# tiva-c.net
KiCad netlist of a schematic drawn in EAGLE
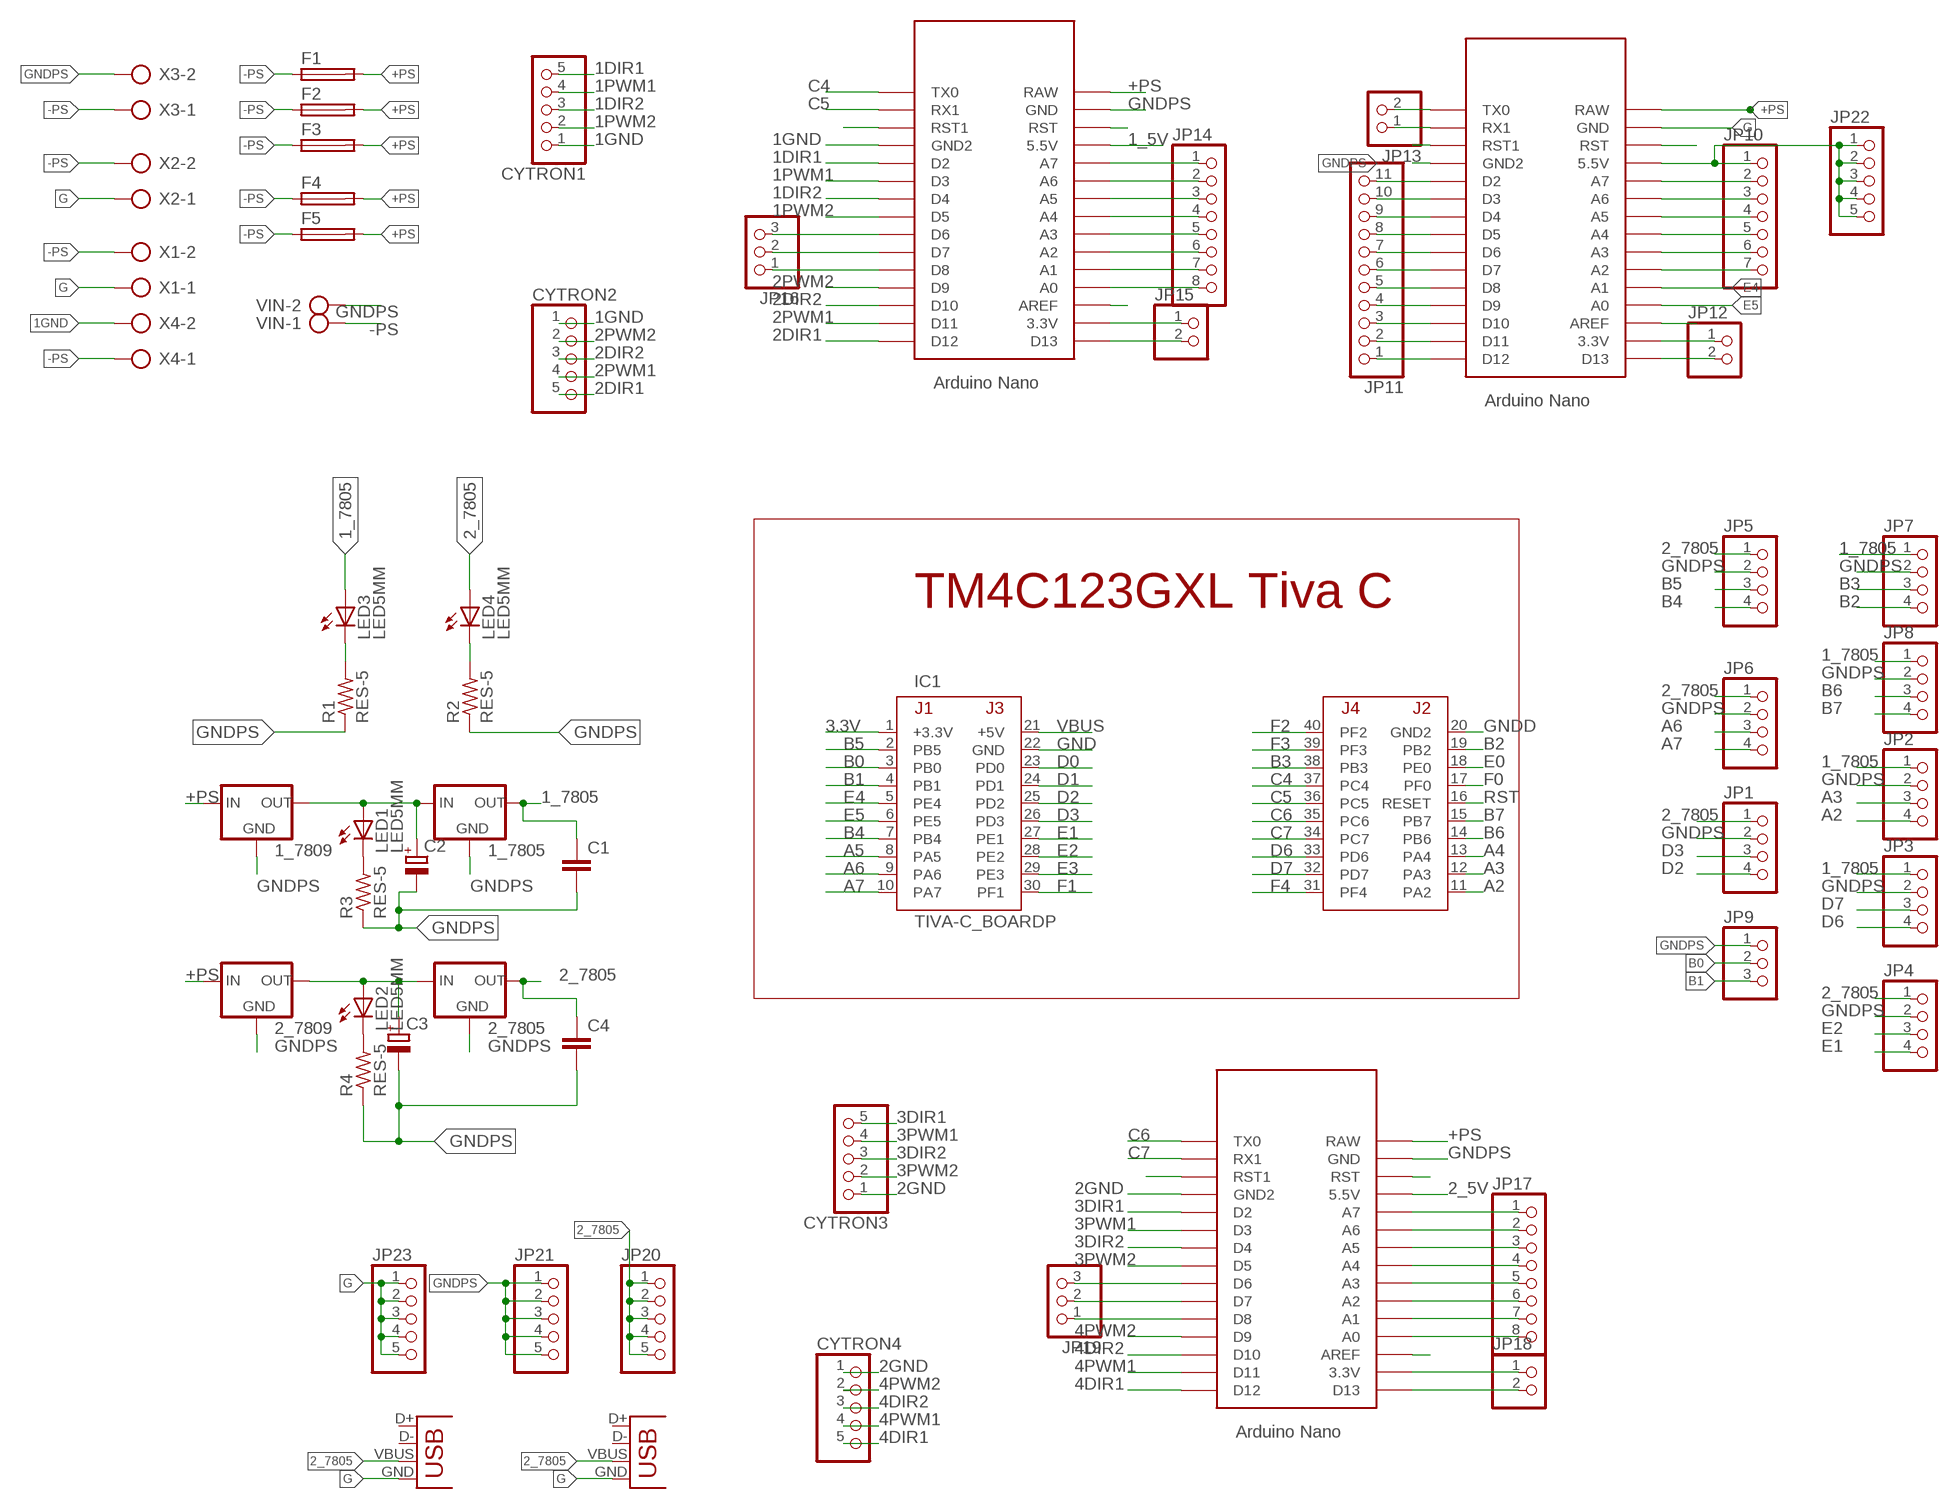
[diagram p0: schematic, sheet 1]

(export (version "E")
  (design (tool "Eeschema 10.0.6"))
  (components
    (comp (ref "1_7805")
      (value "78XXS")
      (footprint "eagle-import:78XXS")
      (libsource (lib "eagle-import") (part "78XXS"))
    )
    (comp (ref "1_7809")
      (value "78XXS")
      (footprint "eagle-import:78XXS")
      (libsource (lib "eagle-import") (part "78XXS"))
    )
    (comp (ref "2_7805")
      (value "78XXS")
      (footprint "eagle-import:78XXS")
      (libsource (lib "eagle-import") (part "78XXS"))
    )
    (comp (ref "2_7809")
      (value "78XXS")
      (footprint "eagle-import:78XXS")
      (libsource (lib "eagle-import") (part "78XXS"))
    )
    (comp (ref "C1")
      (value "CAPACITOR")
      (footprint "eagle-import:C025-025X050")
      (libsource (lib "eagle-import") (part "CAPACITOR"))
    )
    (comp (ref "C2")
      (value "CAP_POL")
      (footprint "eagle-import:E3,5-8")
      (libsource (lib "eagle-import") (part "CAP_POL"))
    )
    (comp (ref "C3")
      (value "CAP_POL")
      (footprint "eagle-import:E3,5-8")
      (libsource (lib "eagle-import") (part "CAP_POL"))
    )
    (comp (ref "C4")
      (value "CAPACITOR")
      (footprint "eagle-import:C025-025X050")
      (libsource (lib "eagle-import") (part "CAPACITOR"))
    )
    (comp (ref "CYTRON1")
      (value "PINHD-1X5")
      (footprint "eagle-import:1X05")
      (libsource (lib "eagle-import") (part "PINHD-1X5"))
    )
    (comp (ref "CYTRON2")
      (value "PINHD-1X5")
      (footprint "eagle-import:1X05")
      (libsource (lib "eagle-import") (part "PINHD-1X5"))
    )
    (comp (ref "CYTRON3")
      (value "PINHD-1X5")
      (footprint "eagle-import:1X05")
      (libsource (lib "eagle-import") (part "PINHD-1X5"))
    )
    (comp (ref "CYTRON4")
      (value "PINHD-1X5")
      (footprint "eagle-import:1X05")
      (libsource (lib "eagle-import") (part "PINHD-1X5"))
    )
    (comp (ref "F1")
      (value "FUSE_HOLDER")
      (footprint "eagle-import:SH22,5A")
      (libsource (lib "eagle-import") (part "FUSE_HOLDER"))
    )
    (comp (ref "F2")
      (value "FUSE_HOLDER")
      (footprint "eagle-import:SH22,5A")
      (libsource (lib "eagle-import") (part "FUSE_HOLDER"))
    )
    (comp (ref "F3")
      (value "FUSE_HOLDER")
      (footprint "eagle-import:SH22,5A")
      (libsource (lib "eagle-import") (part "FUSE_HOLDER"))
    )
    (comp (ref "F4")
      (value "FUSE_HOLDER")
      (footprint "eagle-import:SH22,5A")
      (libsource (lib "eagle-import") (part "FUSE_HOLDER"))
    )
    (comp (ref "F5")
      (value "FUSE_HOLDER")
      (footprint "eagle-import:SH22,5A")
      (libsource (lib "eagle-import") (part "FUSE_HOLDER"))
    )
    (comp (ref "IC1")
      (value "TIVA-C_BOARDP")
      (footprint "eagle-import:TM4C123LAUNCHPAD")
      (fields (field (name "MF") "Texas Instruments") (field (name "MP") "EK-TM4C123GXL"))
      (libsource (lib "eagle-import") (part "TIVA-C_BOARDP"))
    )
    (comp (ref "JP1")
      (value "PINHD-1X4")
      (footprint "eagle-import:1X04")
      (libsource (lib "eagle-import") (part "PINHD-1X4"))
    )
    (comp (ref "JP2")
      (value "PINHD-1X4")
      (footprint "eagle-import:1X04")
      (libsource (lib "eagle-import") (part "PINHD-1X4"))
    )
    (comp (ref "JP3")
      (value "PINHD-1X4")
      (footprint "eagle-import:1X04")
      (libsource (lib "eagle-import") (part "PINHD-1X4"))
    )
    (comp (ref "JP4")
      (value "PINHD-1X4")
      (footprint "eagle-import:1X04")
      (libsource (lib "eagle-import") (part "PINHD-1X4"))
    )
    (comp (ref "JP5")
      (value "PINHD-1X4")
      (footprint "eagle-import:1X04")
      (libsource (lib "eagle-import") (part "PINHD-1X4"))
    )
    (comp (ref "JP6")
      (value "PINHD-1X4")
      (footprint "eagle-import:1X04")
      (libsource (lib "eagle-import") (part "PINHD-1X4"))
    )
    (comp (ref "JP7")
      (value "PINHD-1X4")
      (footprint "eagle-import:1X04")
      (libsource (lib "eagle-import") (part "PINHD-1X4"))
    )
    (comp (ref "JP8")
      (value "PINHD-1X4")
      (footprint "eagle-import:1X04")
      (libsource (lib "eagle-import") (part "PINHD-1X4"))
    )
    (comp (ref "JP9")
      (value "PINHD-1X3")
      (footprint "eagle-import:1X03")
      (libsource (lib "eagle-import") (part "PINHD-1X3"))
    )
    (comp (ref "JP10")
      (value "PINHD-1X7")
      (footprint "eagle-import:1X07")
      (libsource (lib "eagle-import") (part "PINHD-1X7"))
    )
    (comp (ref "JP11")
      (value "PINHD-1X11")
      (footprint "eagle-import:1X11")
      (libsource (lib "eagle-import") (part "PINHD-1X11"))
    )
    (comp (ref "JP12")
      (value "PINHD-1X2")
      (footprint "eagle-import:1X02")
      (libsource (lib "eagle-import") (part "PINHD-1X2"))
    )
    (comp (ref "JP13")
      (value "PINHD-1X2")
      (footprint "eagle-import:1X02")
      (libsource (lib "eagle-import") (part "PINHD-1X2"))
    )
    (comp (ref "JP14")
      (value "PINHD-1X8")
      (footprint "eagle-import:1X08")
      (libsource (lib "eagle-import") (part "PINHD-1X8"))
    )
    (comp (ref "JP15")
      (value "PINHD-1X2")
      (footprint "eagle-import:1X02")
      (libsource (lib "eagle-import") (part "PINHD-1X2"))
    )
    (comp (ref "JP16")
      (value "PINHD-1X3")
      (footprint "eagle-import:1X03")
      (libsource (lib "eagle-import") (part "PINHD-1X3"))
    )
    (comp (ref "JP17")
      (value "PINHD-1X8")
      (footprint "eagle-import:1X08")
      (libsource (lib "eagle-import") (part "PINHD-1X8"))
    )
    (comp (ref "JP18")
      (value "PINHD-1X2")
      (footprint "eagle-import:1X02")
      (libsource (lib "eagle-import") (part "PINHD-1X2"))
    )
    (comp (ref "JP19")
      (value "PINHD-1X3")
      (footprint "eagle-import:1X03")
      (libsource (lib "eagle-import") (part "PINHD-1X3"))
    )
    (comp (ref "JP20")
      (value "PINHD-1X5")
      (footprint "eagle-import:1X05")
      (libsource (lib "eagle-import") (part "PINHD-1X5"))
    )
    (comp (ref "JP21")
      (value "PINHD-1X5")
      (footprint "eagle-import:1X05")
      (libsource (lib "eagle-import") (part "PINHD-1X5"))
    )
    (comp (ref "JP22")
      (value "PINHD-1X5")
      (footprint "eagle-import:1X05")
      (libsource (lib "eagle-import") (part "PINHD-1X5"))
    )
    (comp (ref "JP23")
      (value "PINHD-1X5")
      (footprint "eagle-import:1X05")
      (libsource (lib "eagle-import") (part "PINHD-1X5"))
    )
    (comp (ref "LED1")
      (value "LED5MM")
      (footprint "eagle-import:LED5MM")
      (libsource (lib "eagle-import") (part "LED5MM"))
    )
    (comp (ref "LED2")
      (value "LED5MM")
      (footprint "eagle-import:LED5MM")
      (libsource (lib "eagle-import") (part "LED5MM"))
    )
    (comp (ref "LED3")
      (value "LED5MM")
      (footprint "eagle-import:LED5MM")
      (libsource (lib "eagle-import") (part "LED5MM"))
    )
    (comp (ref "LED4")
      (value "LED5MM")
      (footprint "eagle-import:LED5MM")
      (libsource (lib "eagle-import") (part "LED5MM"))
    )
    (comp (ref "R1")
      (value "RES-5")
      (footprint "eagle-import:0204_5")
      (libsource (lib "eagle-import") (part "RES-5"))
    )
    (comp (ref "R2")
      (value "RES-5")
      (footprint "eagle-import:0204_5")
      (libsource (lib "eagle-import") (part "RES-5"))
    )
    (comp (ref "R3")
      (value "RES-5")
      (footprint "eagle-import:0204_5")
      (libsource (lib "eagle-import") (part "RES-5"))
    )
    (comp (ref "R4")
      (value "RES-5")
      (footprint "eagle-import:0204_5")
      (libsource (lib "eagle-import") (part "RES-5"))
    )
    (comp (ref "U$1")
      (value "ARDUINO_NANO")
      (footprint "eagle-import:NANO")
      (libsource (lib "eagle-import") (part "ARDUINO_NANO"))
    )
    (comp (ref "U$2")
      (value "ARDUINO_NANO")
      (footprint "eagle-import:NANO")
      (libsource (lib "eagle-import") (part "ARDUINO_NANO"))
    )
    (comp (ref "U$3")
      (value "ARDUINO_NANO")
      (footprint "eagle-import:NANO")
      (libsource (lib "eagle-import") (part "ARDUINO_NANO"))
    )
    (comp (ref "VIN")
      (value "CON_PTR_2(V_2)")
      (footprint "eagle-import:AK300_2")
      (libsource (lib "eagle-import") (part "CON_PTR_2(V_2)"))
    )
    (comp (ref "X1")
      (value "CON_PTR_2(V_2)")
      (footprint "eagle-import:AK300_2")
      (libsource (lib "eagle-import") (part "CON_PTR_2(V_2)"))
    )
    (comp (ref "X2")
      (value "CON_PTR_2(V_2)")
      (footprint "eagle-import:AK300_2")
      (libsource (lib "eagle-import") (part "CON_PTR_2(V_2)"))
    )
    (comp (ref "X3")
      (value "CON_PTR_2(V_2)")
      (footprint "eagle-import:AK300_2")
      (libsource (lib "eagle-import") (part "CON_PTR_2(V_2)"))
    )
    (comp (ref "X4")
      (value "CON_PTR_2(V_2)")
      (footprint "eagle-import:AK300_2")
      (libsource (lib "eagle-import") (part "CON_PTR_2(V_2)"))
    )
    (comp (ref "X5")
      (value "USB-A-H")
      (footprint "eagle-import:USB-A-H")
      (libsource (lib "eagle-import") (part "USB-A-H"))
    )
    (comp (ref "X6")
      (value "USB-A-H")
      (footprint "eagle-import:USB-A-H")
      (libsource (lib "eagle-import") (part "USB-A-H"))
    )
  )
  (nets
    (net (code "1") (name "+PS") (class "Default")
      (node (ref "1_7809") (pin "IN") (pinfunction "IN_IN") (pintype "input"))
      (node (ref "2_7809") (pin "IN") (pinfunction "IN_IN") (pintype "input"))
      (node (ref "F1") (pin "2") (pinfunction "2_2") (pintype "passive"))
      (node (ref "F2") (pin "2") (pinfunction "2_2") (pintype "passive"))
      (node (ref "F3") (pin "2") (pinfunction "2_2") (pintype "passive"))
      (node (ref "F4") (pin "2") (pinfunction "2_2") (pintype "passive"))
      (node (ref "F5") (pin "2") (pinfunction "2_2") (pintype "passive"))
      (node (ref "U$1") (pin "RAW") (pinfunction "RAW_RAW") (pintype "bidirectional"))
      (node (ref "U$2") (pin "RAW") (pinfunction "RAW_RAW") (pintype "bidirectional"))
      (node (ref "U$3") (pin "RAW") (pinfunction "RAW_RAW") (pintype "bidirectional"))
    )
    (net (code "2") (name "-PS") (class "Default")
      (node (ref "F1") (pin "1") (pinfunction "1_1") (pintype "passive"))
      (node (ref "F2") (pin "1") (pinfunction "1_1") (pintype "passive"))
      (node (ref "F3") (pin "1") (pinfunction "1_1") (pintype "passive"))
      (node (ref "F4") (pin "1") (pinfunction "1_1") (pintype "passive"))
      (node (ref "F5") (pin "1") (pinfunction "1_1") (pintype "passive"))
      (node (ref "VIN") (pin "1") (pinfunction "KL_1") (pintype "passive"))
      (node (ref "X1") (pin "2") (pinfunction "KL_2") (pintype "passive"))
      (node (ref "X2") (pin "2") (pinfunction "KL_2") (pintype "passive"))
      (node (ref "X3") (pin "1") (pinfunction "KL_1") (pintype "passive"))
      (node (ref "X4") (pin "1") (pinfunction "KL_1") (pintype "passive"))
    )
    (net (code "3") (name "/1DIR1") (class "Default")
      (node (ref "CYTRON1") (pin "5") (pinfunction "5_5") (pintype "passive"))
      (node (ref "U$3") (pin "D2") (pinfunction "D2_D2") (pintype "bidirectional"))
    )
    (net (code "4") (name "/1DIR2") (class "Default")
      (node (ref "CYTRON1") (pin "3") (pinfunction "3_3") (pintype "passive"))
      (node (ref "U$3") (pin "D4") (pinfunction "D4_D4") (pintype "bidirectional"))
    )
    (net (code "5") (name "/1PWM1") (class "Default")
      (node (ref "CYTRON1") (pin "4") (pinfunction "4_4") (pintype "passive"))
      (node (ref "U$3") (pin "D3") (pinfunction "D3_D3") (pintype "bidirectional"))
    )
    (net (code "6") (name "/1PWM2") (class "Default")
      (node (ref "CYTRON1") (pin "2") (pinfunction "2_2") (pintype "passive"))
      (node (ref "U$3") (pin "D5") (pinfunction "D5_D5") (pintype "bidirectional"))
    )
    (net (code "7") (name "/1_5V") (class "Default")
      (node (ref "U$3") (pin "5V") (pinfunction "5.5V_5V") (pintype "bidirectional"))
    )
    (net (code "8") (name "/2DIR1") (class "Default")
      (node (ref "CYTRON2") (pin "5") (pinfunction "5_5") (pintype "passive"))
      (node (ref "U$3") (pin "D12") (pinfunction "D12_D12") (pintype "bidirectional"))
    )
    (net (code "9") (name "/2DIR2") (class "Default")
      (node (ref "CYTRON2") (pin "3") (pinfunction "3_3") (pintype "passive"))
      (node (ref "U$3") (pin "D10") (pinfunction "D10_D10") (pintype "bidirectional"))
    )
    (net (code "10") (name "/2GND") (class "Default")
      (node (ref "CYTRON3") (pin "1") (pinfunction "1_1") (pintype "passive"))
      (node (ref "CYTRON4") (pin "1") (pinfunction "1_1") (pintype "passive"))
      (node (ref "U$1") (pin "GND1") (pinfunction "GND2_GND1") (pintype "bidirectional"))
    )
    (net (code "11") (name "/2PWM1") (class "Default")
      (node (ref "CYTRON2") (pin "4") (pinfunction "4_4") (pintype "passive"))
      (node (ref "U$3") (pin "D11") (pinfunction "D11_D11") (pintype "bidirectional"))
    )
    (net (code "12") (name "/2PWM2") (class "Default")
      (node (ref "CYTRON2") (pin "2") (pinfunction "2_2") (pintype "passive"))
      (node (ref "U$3") (pin "D9") (pinfunction "D9_D9") (pintype "bidirectional"))
    )
    (net (code "13") (name "/2_5V") (class "Default")
      (node (ref "U$1") (pin "5V") (pinfunction "5.5V_5V") (pintype "bidirectional"))
    )
    (net (code "14") (name "/3.3V") (class "Default")
      (node (ref "IC1") (pin "1") (pinfunction "+3.3V_1") (pintype "power_in"))
    )
    (net (code "15") (name "/3DIR1") (class "Default")
      (node (ref "CYTRON3") (pin "5") (pinfunction "5_5") (pintype "passive"))
      (node (ref "U$1") (pin "D2") (pinfunction "D2_D2") (pintype "bidirectional"))
    )
    (net (code "16") (name "/3DIR2") (class "Default")
      (node (ref "CYTRON3") (pin "3") (pinfunction "3_3") (pintype "passive"))
      (node (ref "U$1") (pin "D4") (pinfunction "D4_D4") (pintype "bidirectional"))
    )
    (net (code "17") (name "/3PWM1") (class "Default")
      (node (ref "CYTRON3") (pin "4") (pinfunction "4_4") (pintype "passive"))
      (node (ref "U$1") (pin "D3") (pinfunction "D3_D3") (pintype "bidirectional"))
    )
    (net (code "18") (name "/3PWM2") (class "Default")
      (node (ref "CYTRON3") (pin "2") (pinfunction "2_2") (pintype "passive"))
      (node (ref "U$1") (pin "D5") (pinfunction "D5_D5") (pintype "bidirectional"))
    )
    (net (code "19") (name "/4DIR1") (class "Default")
      (node (ref "CYTRON4") (pin "5") (pinfunction "5_5") (pintype "passive"))
      (node (ref "U$1") (pin "D12") (pinfunction "D12_D12") (pintype "bidirectional"))
    )
    (net (code "20") (name "/4DIR2") (class "Default")
      (node (ref "CYTRON4") (pin "3") (pinfunction "3_3") (pintype "passive"))
      (node (ref "U$1") (pin "D10") (pinfunction "D10_D10") (pintype "bidirectional"))
    )
    (net (code "21") (name "/4PWM1") (class "Default")
      (node (ref "CYTRON4") (pin "4") (pinfunction "4_4") (pintype "passive"))
      (node (ref "U$1") (pin "D11") (pinfunction "D11_D11") (pintype "bidirectional"))
    )
    (net (code "22") (name "/4PWM2") (class "Default")
      (node (ref "CYTRON4") (pin "2") (pinfunction "2_2") (pintype "passive"))
      (node (ref "U$1") (pin "D9") (pinfunction "D9_D9") (pintype "bidirectional"))
    )
    (net (code "23") (name "/A2") (class "Default")
      (node (ref "IC1") (pin "11") (pinfunction "PA2_11") (pintype "bidirectional"))
      (node (ref "JP2") (pin "4") (pinfunction "4_4") (pintype "passive"))
    )
    (net (code "24") (name "/A3") (class "Default")
      (node (ref "IC1") (pin "12") (pinfunction "PA3_12") (pintype "bidirectional"))
      (node (ref "JP2") (pin "3") (pinfunction "3_3") (pintype "passive"))
    )
    (net (code "25") (name "/A4") (class "Default")
      (node (ref "IC1") (pin "13") (pinfunction "PA4_13") (pintype "bidirectional"))
    )
    (net (code "26") (name "/A5") (class "Default")
      (node (ref "IC1") (pin "8") (pinfunction "PA5_8") (pintype "bidirectional"))
    )
    (net (code "27") (name "/A6") (class "Default")
      (node (ref "IC1") (pin "9") (pinfunction "PA6_9") (pintype "bidirectional"))
      (node (ref "JP6") (pin "3") (pinfunction "3_3") (pintype "passive"))
    )
    (net (code "28") (name "/A7") (class "Default")
      (node (ref "IC1") (pin "10") (pinfunction "PA7_10") (pintype "bidirectional"))
      (node (ref "JP6") (pin "4") (pinfunction "4_4") (pintype "passive"))
    )
    (net (code "29") (name "/B2") (class "Default")
      (node (ref "IC1") (pin "19") (pinfunction "PB2_19") (pintype "bidirectional"))
      (node (ref "JP7") (pin "4") (pinfunction "4_4") (pintype "passive"))
    )
    (net (code "30") (name "/B3") (class "Default")
      (node (ref "IC1") (pin "38") (pinfunction "PB3_38") (pintype "bidirectional"))
      (node (ref "JP7") (pin "3") (pinfunction "3_3") (pintype "passive"))
    )
    (net (code "31") (name "/B4") (class "Default")
      (node (ref "IC1") (pin "7") (pinfunction "PB4_7") (pintype "bidirectional"))
      (node (ref "JP5") (pin "4") (pinfunction "4_4") (pintype "passive"))
    )
    (net (code "32") (name "/B5") (class "Default")
      (node (ref "IC1") (pin "2") (pinfunction "PB5_2") (pintype "bidirectional"))
      (node (ref "JP5") (pin "3") (pinfunction "3_3") (pintype "passive"))
    )
    (net (code "33") (name "/B6") (class "Default")
      (node (ref "IC1") (pin "14") (pinfunction "PB6_14") (pintype "bidirectional"))
      (node (ref "JP8") (pin "3") (pinfunction "3_3") (pintype "passive"))
    )
    (net (code "34") (name "/B7") (class "Default")
      (node (ref "IC1") (pin "15") (pinfunction "PB7_15") (pintype "bidirectional"))
      (node (ref "JP8") (pin "4") (pinfunction "4_4") (pintype "passive"))
    )
    (net (code "35") (name "/C4") (class "Default")
      (node (ref "IC1") (pin "37") (pinfunction "PC4_37") (pintype "bidirectional"))
      (node (ref "U$3") (pin "TX0") (pinfunction "TX0_TX0") (pintype "bidirectional"))
    )
    (net (code "36") (name "/C5") (class "Default")
      (node (ref "IC1") (pin "36") (pinfunction "PC5_36") (pintype "bidirectional"))
      (node (ref "U$3") (pin "RX1") (pinfunction "RX1_RX1") (pintype "bidirectional"))
    )
    (net (code "37") (name "/C6") (class "Default")
      (node (ref "IC1") (pin "35") (pinfunction "PC6_35") (pintype "bidirectional"))
      (node (ref "U$1") (pin "TX0") (pinfunction "TX0_TX0") (pintype "bidirectional"))
    )
    (net (code "38") (name "/C7") (class "Default")
      (node (ref "IC1") (pin "34") (pinfunction "PC7_34") (pintype "bidirectional"))
      (node (ref "U$1") (pin "RX1") (pinfunction "RX1_RX1") (pintype "bidirectional"))
    )
    (net (code "39") (name "/D0") (class "Default")
      (node (ref "IC1") (pin "23") (pinfunction "PD0_23") (pintype "bidirectional"))
    )
    (net (code "40") (name "/D1") (class "Default")
      (node (ref "IC1") (pin "24") (pinfunction "PD1_24") (pintype "bidirectional"))
    )
    (net (code "41") (name "/D2") (class "Default")
      (node (ref "IC1") (pin "25") (pinfunction "PD2_25") (pintype "bidirectional"))
      (node (ref "JP1") (pin "4") (pinfunction "4_4") (pintype "passive"))
    )
    (net (code "42") (name "/D3") (class "Default")
      (node (ref "IC1") (pin "26") (pinfunction "PD3_26") (pintype "bidirectional"))
      (node (ref "JP1") (pin "3") (pinfunction "3_3") (pintype "passive"))
    )
    (net (code "43") (name "/D6") (class "Default")
      (node (ref "IC1") (pin "33") (pinfunction "PD6_33") (pintype "bidirectional"))
      (node (ref "JP3") (pin "4") (pinfunction "4_4") (pintype "passive"))
    )
    (net (code "44") (name "/D7") (class "Default")
      (node (ref "IC1") (pin "32") (pinfunction "PD7_32") (pintype "bidirectional"))
      (node (ref "JP3") (pin "3") (pinfunction "3_3") (pintype "passive"))
    )
    (net (code "45") (name "/E0") (class "Default")
      (node (ref "IC1") (pin "18") (pinfunction "PE0_18") (pintype "bidirectional"))
    )
    (net (code "46") (name "/E1") (class "Default")
      (node (ref "IC1") (pin "27") (pinfunction "PE1_27") (pintype "bidirectional"))
      (node (ref "JP4") (pin "4") (pinfunction "4_4") (pintype "passive"))
    )
    (net (code "47") (name "/E2") (class "Default")
      (node (ref "IC1") (pin "28") (pinfunction "PE2_28") (pintype "bidirectional"))
      (node (ref "JP4") (pin "3") (pinfunction "3_3") (pintype "passive"))
    )
    (net (code "48") (name "/E3") (class "Default")
      (node (ref "IC1") (pin "29") (pinfunction "PE3_29") (pintype "bidirectional"))
    )
    (net (code "49") (name "/F0") (class "Default")
      (node (ref "IC1") (pin "17") (pinfunction "PF0_17") (pintype "bidirectional"))
    )
    (net (code "50") (name "/F1") (class "Default")
      (node (ref "IC1") (pin "30") (pinfunction "PF1_30") (pintype "bidirectional"))
    )
    (net (code "51") (name "/F2") (class "Default")
      (node (ref "IC1") (pin "40") (pinfunction "PF2_40") (pintype "bidirectional"))
    )
    (net (code "52") (name "/F3") (class "Default")
      (node (ref "IC1") (pin "39") (pinfunction "PF3_39") (pintype "bidirectional"))
    )
    (net (code "53") (name "/F4") (class "Default")
      (node (ref "IC1") (pin "31") (pinfunction "PF4_31") (pintype "bidirectional"))
    )
    (net (code "54") (name "/GND") (class "Default")
      (node (ref "IC1") (pin "22") (pinfunction "GND_22") (pintype "power_in"))
    )
    (net (code "55") (name "/GNDD") (class "Default")
      (node (ref "IC1") (pin "20") (pinfunction "GND2_20") (pintype "power_in"))
    )
    (net (code "56") (name "/RST") (class "Default")
      (node (ref "IC1") (pin "16") (pinfunction "RESET_16") (pintype "input"))
    )
    (net (code "57") (name "/VBUS") (class "Default")
      (node (ref "IC1") (pin "21") (pinfunction "+5V_21") (pintype "power_in"))
    )
    (net (code "58") (name "1GND") (class "Default")
      (node (ref "CYTRON1") (pin "1") (pinfunction "1_1") (pintype "passive"))
      (node (ref "CYTRON2") (pin "1") (pinfunction "1_1") (pintype "passive"))
      (node (ref "U$3") (pin "GND1") (pinfunction "GND2_GND1") (pintype "bidirectional"))
      (node (ref "X4") (pin "2") (pinfunction "KL_2") (pintype "passive"))
    )
    (net (code "59") (name "1_7805") (class "Default")
      (node (ref "1_7805") (pin "OUT") (pinfunction "OUT_OUT") (pintype "passive"))
      (node (ref "C1") (pin "1") (pinfunction "1_1") (pintype "passive"))
      (node (ref "JP2") (pin "1") (pinfunction "1_1") (pintype "passive"))
      (node (ref "JP3") (pin "1") (pinfunction "1_1") (pintype "passive"))
      (node (ref "JP7") (pin "1") (pinfunction "1_1") (pintype "passive"))
      (node (ref "JP8") (pin "1") (pinfunction "1_1") (pintype "passive"))
      (node (ref "LED3") (pin "A") (pinfunction "A_A") (pintype "passive"))
    )
    (net (code "60") (name "2_7805") (class "Default")
      (node (ref "2_7805") (pin "OUT") (pinfunction "OUT_OUT") (pintype "passive"))
      (node (ref "C4") (pin "1") (pinfunction "1_1") (pintype "passive"))
      (node (ref "JP1") (pin "1") (pinfunction "1_1") (pintype "passive"))
      (node (ref "JP20") (pin "1") (pinfunction "1_1") (pintype "passive"))
      (node (ref "JP20") (pin "2") (pinfunction "2_2") (pintype "passive"))
      (node (ref "JP20") (pin "3") (pinfunction "3_3") (pintype "passive"))
      (node (ref "JP20") (pin "4") (pinfunction "4_4") (pintype "passive"))
      (node (ref "JP20") (pin "5") (pinfunction "5_5") (pintype "passive"))
      (node (ref "JP4") (pin "1") (pinfunction "1_1") (pintype "passive"))
      (node (ref "JP5") (pin "1") (pinfunction "1_1") (pintype "passive"))
      (node (ref "JP6") (pin "1") (pinfunction "1_1") (pintype "passive"))
      (node (ref "LED4") (pin "A") (pinfunction "A_A") (pintype "passive"))
      (node (ref "X5") (pin "VBUS") (pinfunction "VBUS_VBUS") (pintype "bidirectional"))
      (node (ref "X6") (pin "VBUS") (pinfunction "VBUS_VBUS") (pintype "bidirectional"))
    )
    (net (code "61") (name "B0") (class "Default")
      (node (ref "IC1") (pin "3") (pinfunction "PB0_3") (pintype "bidirectional"))
      (node (ref "JP9") (pin "2") (pinfunction "2_2") (pintype "passive"))
    )
    (net (code "62") (name "B1") (class "Default")
      (node (ref "IC1") (pin "4") (pinfunction "PB1_4") (pintype "bidirectional"))
      (node (ref "JP9") (pin "3") (pinfunction "3_3") (pintype "passive"))
    )
    (net (code "63") (name "E4") (class "Default")
      (node (ref "IC1") (pin "5") (pinfunction "PE4_5") (pintype "bidirectional"))
      (node (ref "U$2") (pin "A1") (pinfunction "A1_A1") (pintype "bidirectional"))
    )
    (net (code "64") (name "E5") (class "Default")
      (node (ref "IC1") (pin "6") (pinfunction "PE5_6") (pintype "bidirectional"))
      (node (ref "U$2") (pin "A0") (pinfunction "A0_A0") (pintype "bidirectional"))
    )
    (net (code "65") (name "G") (class "Default")
      (node (ref "JP23") (pin "1") (pinfunction "1_1") (pintype "passive"))
      (node (ref "JP23") (pin "2") (pinfunction "2_2") (pintype "passive"))
      (node (ref "JP23") (pin "3") (pinfunction "3_3") (pintype "passive"))
      (node (ref "JP23") (pin "4") (pinfunction "4_4") (pintype "passive"))
      (node (ref "JP23") (pin "5") (pinfunction "5_5") (pintype "passive"))
      (node (ref "U$2") (pin "GND") (pinfunction "GND_GND") (pintype "bidirectional"))
      (node (ref "X1") (pin "1") (pinfunction "KL_1") (pintype "passive"))
      (node (ref "X2") (pin "1") (pinfunction "KL_1") (pintype "passive"))
      (node (ref "X5") (pin "GND") (pinfunction "GND_GND") (pintype "bidirectional"))
      (node (ref "X6") (pin "GND") (pinfunction "GND_GND") (pintype "bidirectional"))
    )
    (net (code "66") (name "GNDPS") (class "Default")
      (node (ref "1_7805") (pin "GND") (pinfunction "GND_GND") (pintype "input"))
      (node (ref "1_7809") (pin "GND") (pinfunction "GND_GND") (pintype "input"))
      (node (ref "2_7805") (pin "GND") (pinfunction "GND_GND") (pintype "input"))
      (node (ref "2_7809") (pin "GND") (pinfunction "GND_GND") (pintype "input"))
      (node (ref "C1") (pin "2") (pinfunction "2_2") (pintype "passive"))
      (node (ref "C2") (pin "-") (pinfunction "-_-") (pintype "passive"))
      (node (ref "C3") (pin "-") (pinfunction "-_-") (pintype "passive"))
      (node (ref "C4") (pin "2") (pinfunction "2_2") (pintype "passive"))
      (node (ref "JP1") (pin "2") (pinfunction "2_2") (pintype "passive"))
      (node (ref "JP2") (pin "2") (pinfunction "2_2") (pintype "passive"))
      (node (ref "JP21") (pin "1") (pinfunction "1_1") (pintype "passive"))
      (node (ref "JP21") (pin "2") (pinfunction "2_2") (pintype "passive"))
      (node (ref "JP21") (pin "3") (pinfunction "3_3") (pintype "passive"))
      (node (ref "JP21") (pin "4") (pinfunction "4_4") (pintype "passive"))
      (node (ref "JP21") (pin "5") (pinfunction "5_5") (pintype "passive"))
      (node (ref "JP3") (pin "2") (pinfunction "2_2") (pintype "passive"))
      (node (ref "JP4") (pin "2") (pinfunction "2_2") (pintype "passive"))
      (node (ref "JP5") (pin "2") (pinfunction "2_2") (pintype "passive"))
      (node (ref "JP6") (pin "2") (pinfunction "2_2") (pintype "passive"))
      (node (ref "JP7") (pin "2") (pinfunction "2_2") (pintype "passive"))
      (node (ref "JP8") (pin "2") (pinfunction "2_2") (pintype "passive"))
      (node (ref "JP9") (pin "1") (pinfunction "1_1") (pintype "passive"))
      (node (ref "R1") (pin "1") (pinfunction "1_1") (pintype "passive"))
      (node (ref "R2") (pin "1") (pinfunction "1_1") (pintype "passive"))
      (node (ref "R3") (pin "1") (pinfunction "1_1") (pintype "passive"))
      (node (ref "R4") (pin "1") (pinfunction "1_1") (pintype "passive"))
      (node (ref "U$1") (pin "GND") (pinfunction "GND_GND") (pintype "bidirectional"))
      (node (ref "U$2") (pin "GND1") (pinfunction "GND2_GND1") (pintype "bidirectional"))
      (node (ref "U$3") (pin "GND") (pinfunction "GND_GND") (pintype "bidirectional"))
      (node (ref "VIN") (pin "2") (pinfunction "KL_2") (pintype "passive"))
      (node (ref "X3") (pin "2") (pinfunction "KL_2") (pintype "passive"))
    )
    (net (code "67") (name "Net-(1_7805-PadIN)") (class "Default")
      (node (ref "1_7805") (pin "IN") (pinfunction "IN_IN") (pintype "input"))
      (node (ref "1_7809") (pin "OUT") (pinfunction "OUT_OUT") (pintype "passive"))
      (node (ref "C2") (pin "+") (pinfunction "+_+") (pintype "passive"))
      (node (ref "LED1") (pin "A") (pinfunction "A_A") (pintype "passive"))
    )
    (net (code "68") (name "Net-(2_7805-PadIN)") (class "Default")
      (node (ref "2_7805") (pin "IN") (pinfunction "IN_IN") (pintype "input"))
      (node (ref "2_7809") (pin "OUT") (pinfunction "OUT_OUT") (pintype "passive"))
      (node (ref "C3") (pin "+") (pinfunction "+_+") (pintype "passive"))
      (node (ref "LED2") (pin "A") (pinfunction "A_A") (pintype "passive"))
    )
    (net (code "69") (name "Net-(JP10-Pad2)") (class "Default")
      (node (ref "JP10") (pin "2") (pinfunction "2_2") (pintype "passive"))
      (node (ref "U$2") (pin "A7") (pinfunction "A7_A7") (pintype "bidirectional"))
    )
    (net (code "70") (name "Net-(JP10-Pad3)") (class "Default")
      (node (ref "JP10") (pin "3") (pinfunction "3_3") (pintype "passive"))
      (node (ref "U$2") (pin "A6") (pinfunction "A6_A6") (pintype "bidirectional"))
    )
    (net (code "71") (name "Net-(JP10-Pad4)") (class "Default")
      (node (ref "JP10") (pin "4") (pinfunction "4_4") (pintype "passive"))
      (node (ref "U$2") (pin "A5") (pinfunction "A5_A5") (pintype "bidirectional"))
    )
    (net (code "72") (name "Net-(JP10-Pad5)") (class "Default")
      (node (ref "JP10") (pin "5") (pinfunction "5_5") (pintype "passive"))
      (node (ref "U$2") (pin "A4") (pinfunction "A4_A4") (pintype "bidirectional"))
    )
    (net (code "73") (name "Net-(JP10-Pad6)") (class "Default")
      (node (ref "JP10") (pin "6") (pinfunction "6_6") (pintype "passive"))
      (node (ref "U$2") (pin "A3") (pinfunction "A3_A3") (pintype "bidirectional"))
    )
    (net (code "74") (name "Net-(JP10-Pad7)") (class "Default")
      (node (ref "JP10") (pin "7") (pinfunction "7_7") (pintype "passive"))
      (node (ref "U$2") (pin "A2") (pinfunction "A2_A2") (pintype "bidirectional"))
    )
    (net (code "75") (name "Net-(JP11-Pad1)") (class "Default")
      (node (ref "JP11") (pin "1") (pinfunction "1_1") (pintype "passive"))
      (node (ref "U$2") (pin "D12") (pinfunction "D12_D12") (pintype "bidirectional"))
    )
    (net (code "76") (name "Net-(JP11-Pad2)") (class "Default")
      (node (ref "JP11") (pin "2") (pinfunction "2_2") (pintype "passive"))
      (node (ref "U$2") (pin "D11") (pinfunction "D11_D11") (pintype "bidirectional"))
    )
    (net (code "77") (name "Net-(JP11-Pad3)") (class "Default")
      (node (ref "JP11") (pin "3") (pinfunction "3_3") (pintype "passive"))
      (node (ref "U$2") (pin "D10") (pinfunction "D10_D10") (pintype "bidirectional"))
    )
    (net (code "78") (name "Net-(JP11-Pad4)") (class "Default")
      (node (ref "JP11") (pin "4") (pinfunction "4_4") (pintype "passive"))
      (node (ref "U$2") (pin "D9") (pinfunction "D9_D9") (pintype "bidirectional"))
    )
    (net (code "79") (name "Net-(JP11-Pad5)") (class "Default")
      (node (ref "JP11") (pin "5") (pinfunction "5_5") (pintype "passive"))
      (node (ref "U$2") (pin "D8") (pinfunction "D8_D8") (pintype "bidirectional"))
    )
    (net (code "80") (name "Net-(JP11-Pad6)") (class "Default")
      (node (ref "JP11") (pin "6") (pinfunction "6_6") (pintype "passive"))
      (node (ref "U$2") (pin "D7") (pinfunction "D7_D7") (pintype "bidirectional"))
    )
    (net (code "81") (name "Net-(JP11-Pad7)") (class "Default")
      (node (ref "JP11") (pin "7") (pinfunction "7_7") (pintype "passive"))
      (node (ref "U$2") (pin "D6") (pinfunction "D6_D6") (pintype "bidirectional"))
    )
    (net (code "82") (name "Net-(JP11-Pad8)") (class "Default")
      (node (ref "JP11") (pin "8") (pinfunction "8_8") (pintype "passive"))
      (node (ref "U$2") (pin "D5") (pinfunction "D5_D5") (pintype "bidirectional"))
    )
    (net (code "83") (name "Net-(JP11-Pad9)") (class "Default")
      (node (ref "JP11") (pin "9") (pinfunction "9_9") (pintype "passive"))
      (node (ref "U$2") (pin "D4") (pinfunction "D4_D4") (pintype "bidirectional"))
    )
    (net (code "84") (name "Net-(JP11-Pad10)") (class "Default")
      (node (ref "JP11") (pin "10") (pinfunction "10_10") (pintype "passive"))
      (node (ref "U$2") (pin "D3") (pinfunction "D3_D3") (pintype "bidirectional"))
    )
    (net (code "85") (name "Net-(JP11-Pad11)") (class "Default")
      (node (ref "JP11") (pin "11") (pinfunction "11_11") (pintype "passive"))
      (node (ref "U$2") (pin "D2") (pinfunction "D2_D2") (pintype "bidirectional"))
    )
    (net (code "86") (name "Net-(JP12-Pad1)") (class "Default")
      (node (ref "JP12") (pin "1") (pinfunction "1_1") (pintype "passive"))
      (node (ref "U$2") (pin "3.3V") (pinfunction "3.3V_3.3V") (pintype "bidirectional"))
    )
    (net (code "87") (name "Net-(JP12-Pad2)") (class "Default")
      (node (ref "JP12") (pin "2") (pinfunction "2_2") (pintype "passive"))
      (node (ref "U$2") (pin "D13") (pinfunction "D13_D13") (pintype "bidirectional"))
    )
    (net (code "88") (name "Net-(JP13-Pad1)") (class "Default")
      (node (ref "JP13") (pin "1") (pinfunction "1_1") (pintype "passive"))
      (node (ref "U$2") (pin "RX1") (pinfunction "RX1_RX1") (pintype "bidirectional"))
    )
    (net (code "89") (name "Net-(JP13-Pad2)") (class "Default")
      (node (ref "JP13") (pin "2") (pinfunction "2_2") (pintype "passive"))
      (node (ref "U$2") (pin "TX0") (pinfunction "TX0_TX0") (pintype "bidirectional"))
    )
    (net (code "90") (name "Net-(JP14-Pad1)") (class "Default")
      (node (ref "JP14") (pin "1") (pinfunction "1_1") (pintype "passive"))
      (node (ref "U$3") (pin "A7") (pinfunction "A7_A7") (pintype "bidirectional"))
    )
    (net (code "91") (name "Net-(JP14-Pad2)") (class "Default")
      (node (ref "JP14") (pin "2") (pinfunction "2_2") (pintype "passive"))
      (node (ref "U$3") (pin "A6") (pinfunction "A6_A6") (pintype "bidirectional"))
    )
    (net (code "92") (name "Net-(JP14-Pad3)") (class "Default")
      (node (ref "JP14") (pin "3") (pinfunction "3_3") (pintype "passive"))
      (node (ref "U$3") (pin "A5") (pinfunction "A5_A5") (pintype "bidirectional"))
    )
    (net (code "93") (name "Net-(JP14-Pad4)") (class "Default")
      (node (ref "JP14") (pin "4") (pinfunction "4_4") (pintype "passive"))
      (node (ref "U$3") (pin "A4") (pinfunction "A4_A4") (pintype "bidirectional"))
    )
    (net (code "94") (name "Net-(JP14-Pad5)") (class "Default")
      (node (ref "JP14") (pin "5") (pinfunction "5_5") (pintype "passive"))
      (node (ref "U$3") (pin "A3") (pinfunction "A3_A3") (pintype "bidirectional"))
    )
    (net (code "95") (name "Net-(JP14-Pad6)") (class "Default")
      (node (ref "JP14") (pin "6") (pinfunction "6_6") (pintype "passive"))
      (node (ref "U$3") (pin "A2") (pinfunction "A2_A2") (pintype "bidirectional"))
    )
    (net (code "96") (name "Net-(JP14-Pad7)") (class "Default")
      (node (ref "JP14") (pin "7") (pinfunction "7_7") (pintype "passive"))
      (node (ref "U$3") (pin "A1") (pinfunction "A1_A1") (pintype "bidirectional"))
    )
    (net (code "97") (name "Net-(JP14-Pad8)") (class "Default")
      (node (ref "JP14") (pin "8") (pinfunction "8_8") (pintype "passive"))
      (node (ref "U$3") (pin "A0") (pinfunction "A0_A0") (pintype "bidirectional"))
    )
    (net (code "98") (name "Net-(JP15-Pad1)") (class "Default")
      (node (ref "JP15") (pin "1") (pinfunction "1_1") (pintype "passive"))
      (node (ref "U$3") (pin "3.3V") (pinfunction "3.3V_3.3V") (pintype "bidirectional"))
    )
    (net (code "99") (name "Net-(JP15-Pad2)") (class "Default")
      (node (ref "JP15") (pin "2") (pinfunction "2_2") (pintype "passive"))
      (node (ref "U$3") (pin "D13") (pinfunction "D13_D13") (pintype "bidirectional"))
    )
    (net (code "100") (name "Net-(JP16-Pad1)") (class "Default")
      (node (ref "JP16") (pin "1") (pinfunction "1_1") (pintype "passive"))
      (node (ref "U$3") (pin "D8") (pinfunction "D8_D8") (pintype "bidirectional"))
    )
    (net (code "101") (name "Net-(JP16-Pad2)") (class "Default")
      (node (ref "JP16") (pin "2") (pinfunction "2_2") (pintype "passive"))
      (node (ref "U$3") (pin "D7") (pinfunction "D7_D7") (pintype "bidirectional"))
    )
    (net (code "102") (name "Net-(JP16-Pad3)") (class "Default")
      (node (ref "JP16") (pin "3") (pinfunction "3_3") (pintype "passive"))
      (node (ref "U$3") (pin "D6") (pinfunction "D6_D6") (pintype "bidirectional"))
    )
    (net (code "103") (name "Net-(JP17-Pad1)") (class "Default")
      (node (ref "JP17") (pin "1") (pinfunction "1_1") (pintype "passive"))
      (node (ref "U$1") (pin "A7") (pinfunction "A7_A7") (pintype "bidirectional"))
    )
    (net (code "104") (name "Net-(JP17-Pad2)") (class "Default")
      (node (ref "JP17") (pin "2") (pinfunction "2_2") (pintype "passive"))
      (node (ref "U$1") (pin "A6") (pinfunction "A6_A6") (pintype "bidirectional"))
    )
    (net (code "105") (name "Net-(JP17-Pad3)") (class "Default")
      (node (ref "JP17") (pin "3") (pinfunction "3_3") (pintype "passive"))
      (node (ref "U$1") (pin "A5") (pinfunction "A5_A5") (pintype "bidirectional"))
    )
    (net (code "106") (name "Net-(JP17-Pad4)") (class "Default")
      (node (ref "JP17") (pin "4") (pinfunction "4_4") (pintype "passive"))
      (node (ref "U$1") (pin "A4") (pinfunction "A4_A4") (pintype "bidirectional"))
    )
    (net (code "107") (name "Net-(JP17-Pad5)") (class "Default")
      (node (ref "JP17") (pin "5") (pinfunction "5_5") (pintype "passive"))
      (node (ref "U$1") (pin "A3") (pinfunction "A3_A3") (pintype "bidirectional"))
    )
    (net (code "108") (name "Net-(JP17-Pad6)") (class "Default")
      (node (ref "JP17") (pin "6") (pinfunction "6_6") (pintype "passive"))
      (node (ref "U$1") (pin "A2") (pinfunction "A2_A2") (pintype "bidirectional"))
    )
    (net (code "109") (name "Net-(JP17-Pad7)") (class "Default")
      (node (ref "JP17") (pin "7") (pinfunction "7_7") (pintype "passive"))
      (node (ref "U$1") (pin "A1") (pinfunction "A1_A1") (pintype "bidirectional"))
    )
    (net (code "110") (name "Net-(JP17-Pad8)") (class "Default")
      (node (ref "JP17") (pin "8") (pinfunction "8_8") (pintype "passive"))
      (node (ref "U$1") (pin "A0") (pinfunction "A0_A0") (pintype "bidirectional"))
    )
    (net (code "111") (name "Net-(JP18-Pad1)") (class "Default")
      (node (ref "JP18") (pin "1") (pinfunction "1_1") (pintype "passive"))
      (node (ref "U$1") (pin "3.3V") (pinfunction "3.3V_3.3V") (pintype "bidirectional"))
    )
    (net (code "112") (name "Net-(JP18-Pad2)") (class "Default")
      (node (ref "JP18") (pin "2") (pinfunction "2_2") (pintype "passive"))
      (node (ref "U$1") (pin "D13") (pinfunction "D13_D13") (pintype "bidirectional"))
    )
    (net (code "113") (name "Net-(JP19-Pad1)") (class "Default")
      (node (ref "JP19") (pin "1") (pinfunction "1_1") (pintype "passive"))
      (node (ref "U$1") (pin "D8") (pinfunction "D8_D8") (pintype "bidirectional"))
    )
    (net (code "114") (name "Net-(JP19-Pad2)") (class "Default")
      (node (ref "JP19") (pin "2") (pinfunction "2_2") (pintype "passive"))
      (node (ref "U$1") (pin "D7") (pinfunction "D7_D7") (pintype "bidirectional"))
    )
    (net (code "115") (name "Net-(JP19-Pad3)") (class "Default")
      (node (ref "JP19") (pin "3") (pinfunction "3_3") (pintype "passive"))
      (node (ref "U$1") (pin "D6") (pinfunction "D6_D6") (pintype "bidirectional"))
    )
    (net (code "116") (name "Net-(LED1-C)") (class "Default")
      (node (ref "LED1") (pin "K") (pinfunction "C_K") (pintype "passive"))
      (node (ref "R3") (pin "2") (pinfunction "2_2") (pintype "passive"))
    )
    (net (code "117") (name "Net-(LED2-C)") (class "Default")
      (node (ref "LED2") (pin "K") (pinfunction "C_K") (pintype "passive"))
      (node (ref "R4") (pin "2") (pinfunction "2_2") (pintype "passive"))
    )
    (net (code "118") (name "Net-(LED3-C)") (class "Default")
      (node (ref "LED3") (pin "K") (pinfunction "C_K") (pintype "passive"))
      (node (ref "R1") (pin "2") (pinfunction "2_2") (pintype "passive"))
    )
    (net (code "119") (name "Net-(LED4-C)") (class "Default")
      (node (ref "LED4") (pin "K") (pinfunction "C_K") (pintype "passive"))
      (node (ref "R2") (pin "2") (pinfunction "2_2") (pintype "passive"))
    )
    (net (code "120") (name "Net-(U$2-5.5V)") (class "Default")
      (node (ref "JP10") (pin "1") (pinfunction "1_1") (pintype "passive"))
      (node (ref "JP22") (pin "1") (pinfunction "1_1") (pintype "passive"))
      (node (ref "JP22") (pin "2") (pinfunction "2_2") (pintype "passive"))
      (node (ref "JP22") (pin "3") (pinfunction "3_3") (pintype "passive"))
      (node (ref "JP22") (pin "4") (pinfunction "4_4") (pintype "passive"))
      (node (ref "JP22") (pin "5") (pinfunction "5_5") (pintype "passive"))
      (node (ref "U$2") (pin "5V") (pinfunction "5.5V_5V") (pintype "bidirectional"))
    )
    (net (code "121") (name "unconnected-(U$1-PadAREF)") (class "Default")
      (node (ref "U$1") (pin "AREF") (pinfunction "AREF_AREF") (pintype "bidirectional"))
    )
    (net (code "122") (name "unconnected-(U$1-PadRST)") (class "Default")
      (node (ref "U$1") (pin "RST") (pinfunction "RST_RST") (pintype "bidirectional"))
    )
    (net (code "123") (name "unconnected-(U$1-PadRST1)") (class "Default")
      (node (ref "U$1") (pin "RST1") (pinfunction "RST1_RST1") (pintype "bidirectional"))
    )
    (net (code "124") (name "unconnected-(U$2-PadAREF)") (class "Default")
      (node (ref "U$2") (pin "AREF") (pinfunction "AREF_AREF") (pintype "bidirectional"))
    )
    (net (code "125") (name "unconnected-(U$2-PadRST)") (class "Default")
      (node (ref "U$2") (pin "RST") (pinfunction "RST_RST") (pintype "bidirectional"))
    )
    (net (code "126") (name "unconnected-(U$2-PadRST1)") (class "Default")
      (node (ref "U$2") (pin "RST1") (pinfunction "RST1_RST1") (pintype "bidirectional"))
    )
    (net (code "127") (name "unconnected-(U$3-PadAREF)") (class "Default")
      (node (ref "U$3") (pin "AREF") (pinfunction "AREF_AREF") (pintype "bidirectional"))
    )
    (net (code "128") (name "unconnected-(U$3-PadRST)") (class "Default")
      (node (ref "U$3") (pin "RST") (pinfunction "RST_RST") (pintype "bidirectional"))
    )
    (net (code "129") (name "unconnected-(U$3-PadRST1)") (class "Default")
      (node (ref "U$3") (pin "RST1") (pinfunction "RST1_RST1") (pintype "bidirectional"))
    )
    (net (code "130") (name "unconnected-(X5-PadD+)") (class "Default")
      (node (ref "X5") (pin "D+") (pinfunction "D+_D+") (pintype "bidirectional"))
    )
    (net (code "131") (name "unconnected-(X5-PadD-)") (class "Default")
      (node (ref "X5") (pin "D-") (pinfunction "D-_D-") (pintype "bidirectional"))
    )
    (net (code "132") (name "unconnected-(X6-PadD+)") (class "Default")
      (node (ref "X6") (pin "D+") (pinfunction "D+_D+") (pintype "bidirectional"))
    )
    (net (code "133") (name "unconnected-(X6-PadD-)") (class "Default")
      (node (ref "X6") (pin "D-") (pinfunction "D-_D-") (pintype "bidirectional"))
    )
  )
)
